# PCB-SLIDER60_v11-16.net
KiCad netlist of a schematic drawn in EAGLE
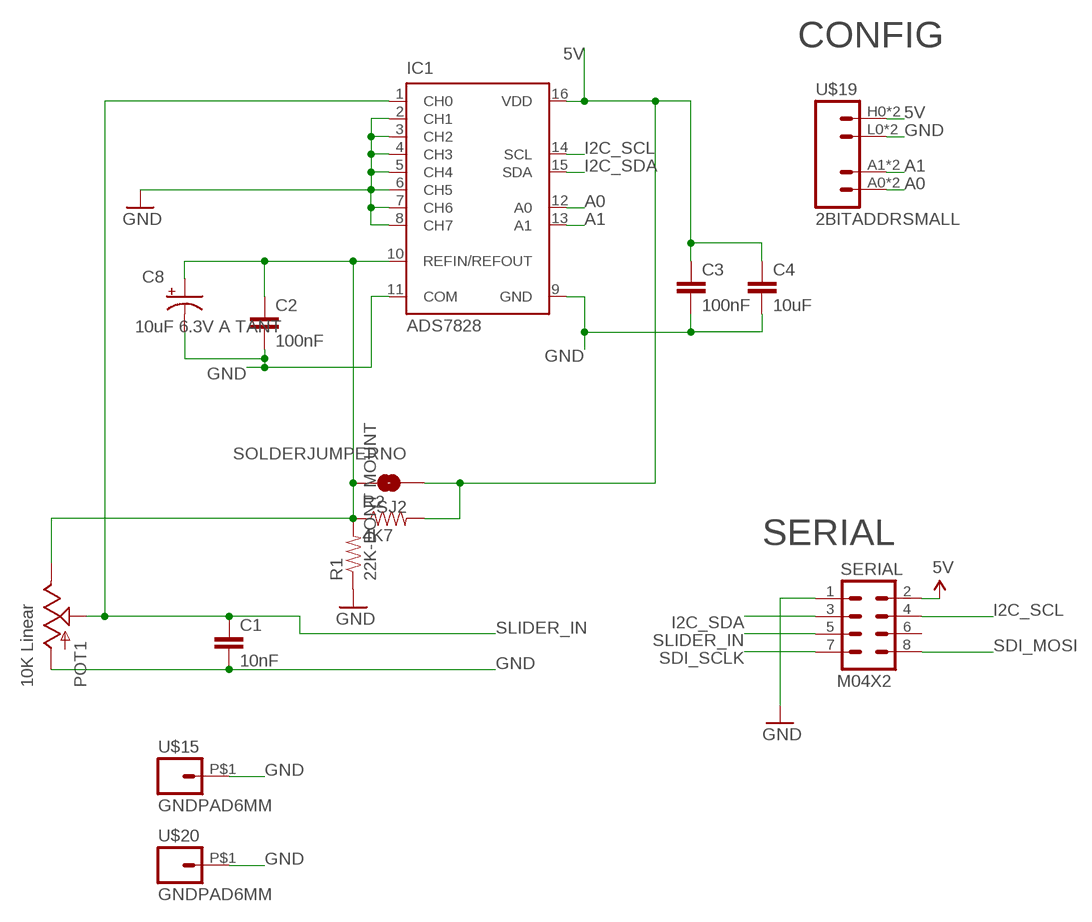
[diagram p0: schematic, sheet 1]

(export (version "E")
  (design (tool "Eeschema 10.0.6"))
  (components
    (comp (ref "C1")
      (value "10nF")
      (footprint "eagle-import:0603-CAP")
      (libsource (lib "eagle-import") (part "CAP0603-CAP"))
    )
    (comp (ref "C2")
      (value "100nF")
      (footprint "eagle-import:0603-CAP")
      (libsource (lib "eagle-import") (part "CAP0603-CAP"))
    )
    (comp (ref "C3")
      (value "100nF")
      (footprint "eagle-import:0603-CAP")
      (libsource (lib "eagle-import") (part "CAP0603-CAP"))
    )
    (comp (ref "C4")
      (value "10uF")
      (footprint "eagle-import:0805")
      (libsource (lib "eagle-import") (part "CAP0805"))
    )
    (comp (ref "C8")
      (value "10uF 6.3V A TANT")
      (footprint "eagle-import:EIA3216")
      (libsource (lib "eagle-import") (part "CAP_POL1206"))
    )
    (comp (ref "IC1")
      (value "ADS7828")
      (footprint "eagle-import:TSSOP16-PW")
      (fields (field (name "MF") "TEXAS INSTRUMENTS") (field (name "MPN") "ADS7828E/250"))
      (libsource (lib "eagle-import") (part "ADS7828"))
    )
    (comp (ref "POT1")
      (value "10K Linear")
      (footprint "eagle-import:SLIDER60")
      (libsource (lib "eagle-import") (part "SLIDER60"))
    )
    (comp (ref "R1")
      (value "22K-DONT MOUNT")
      (footprint "eagle-import:0603-RES")
      (libsource (lib "eagle-import") (part "RESISTOR0603-RES"))
    )
    (comp (ref "R2")
      (value "4K7")
      (footprint "eagle-import:0603-RES")
      (libsource (lib "eagle-import") (part "RESISTOR0603-RES"))
    )
    (comp (ref "SERIAL")
      (value "M04X2")
      (footprint "eagle-import:2X4")
      (libsource (lib "eagle-import") (part "M04X2"))
    )
    (comp (ref "SJ2")
      (value "SOLDERJUMPERNO")
      (footprint "eagle-import:SJ_2S-NO")
      (libsource (lib "eagle-import") (part "SOLDERJUMPERNO"))
    )
    (comp (ref "U$15")
      (value "GNDPAD6MM")
      (footprint "eagle-import:3.2MMPAD6MM")
      (libsource (lib "eagle-import") (part "GNDPAD6MM"))
    )
    (comp (ref "U$19")
      (value "2BITADDRSMALL")
      (footprint "eagle-import:2BITADDR_SMALL")
      (libsource (lib "eagle-import") (part "2BITADDRSMALL"))
    )
    (comp (ref "U$20")
      (value "GNDPAD6MM")
      (footprint "eagle-import:3.2MMPAD6MM")
      (libsource (lib "eagle-import") (part "GNDPAD6MM"))
    )
  )
  (nets
    (net (code "1") (name "/A0") (class "Default")
      (node (ref "IC1") (pin "12") (pinfunction "A0_12") (pintype "input"))
      (node (ref "U$19") (pin "A0") (pinfunction "A1_A0") (pintype "passive"))
      (node (ref "U$19") (pin "AS0") (pinfunction "A1_AS0") (pintype "passive"))
    )
    (net (code "2") (name "/A1") (class "Default")
      (node (ref "IC1") (pin "13") (pinfunction "A1_13") (pintype "input"))
      (node (ref "U$19") (pin "A1") (pinfunction "A2_A1") (pintype "passive"))
      (node (ref "U$19") (pin "AS1") (pinfunction "A2_AS1") (pintype "passive"))
    )
    (net (code "3") (name "/I2C_SCL") (class "Default")
      (node (ref "IC1") (pin "14") (pinfunction "SCL_14") (pintype "input"))
      (node (ref "SERIAL") (pin "4") (pinfunction "4_4") (pintype "passive"))
    )
    (net (code "4") (name "/I2C_SDA") (class "Default")
      (node (ref "IC1") (pin "15") (pinfunction "SDA_15") (pintype "bidirectional"))
      (node (ref "SERIAL") (pin "3") (pinfunction "3_3") (pintype "passive"))
    )
    (net (code "5") (name "/SDI_MOSI") (class "Default")
      (node (ref "SERIAL") (pin "8") (pinfunction "8_8") (pintype "passive"))
    )
    (net (code "6") (name "/SDI_SCLK") (class "Default")
      (node (ref "SERIAL") (pin "7") (pinfunction "7_7") (pintype "passive"))
    )
    (net (code "7") (name "/SLIDER_IN") (class "Default")
      (node (ref "C1") (pin "1") (pinfunction "1_1") (pintype "passive"))
      (node (ref "IC1") (pin "1") (pinfunction "CH0_1") (pintype "input"))
      (node (ref "POT1") (pin "2A") (pinfunction "S_2A") (pintype "passive"))
      (node (ref "SERIAL") (pin "5") (pinfunction "5_5") (pintype "passive"))
    )
    (net (code "8") (name "5V") (class "Default")
      (node (ref "C3") (pin "1") (pinfunction "1_1") (pintype "passive"))
      (node (ref "C4") (pin "1") (pinfunction "1_1") (pintype "passive"))
      (node (ref "IC1") (pin "16") (pinfunction "VDD_16") (pintype "power_in"))
      (node (ref "R2") (pin "2") (pinfunction "2_2") (pintype "passive"))
      (node (ref "SERIAL") (pin "2") (pinfunction "2_2") (pintype "passive"))
      (node (ref "SJ2") (pin "1") (pinfunction "1_1") (pintype "passive"))
      (node (ref "U$19") (pin "H0") (pinfunction "VCC_H0") (pintype "passive"))
      (node (ref "U$19") (pin "H1") (pinfunction "VCC_H1") (pintype "passive"))
    )
    (net (code "9") (name "GND") (class "Default")
      (node (ref "C1") (pin "2") (pinfunction "2_2") (pintype "passive"))
      (node (ref "C2") (pin "2") (pinfunction "2_2") (pintype "passive"))
      (node (ref "C3") (pin "2") (pinfunction "2_2") (pintype "passive"))
      (node (ref "C4") (pin "2") (pinfunction "2_2") (pintype "passive"))
      (node (ref "C8") (pin "C") (pinfunction "-_C") (pintype "passive"))
      (node (ref "IC1") (pin "11") (pinfunction "COM_11") (pintype "input"))
      (node (ref "IC1") (pin "2") (pinfunction "CH1_2") (pintype "input"))
      (node (ref "IC1") (pin "3") (pinfunction "CH2_3") (pintype "input"))
      (node (ref "IC1") (pin "4") (pinfunction "CH3_4") (pintype "input"))
      (node (ref "IC1") (pin "5") (pinfunction "CH4_5") (pintype "input"))
      (node (ref "IC1") (pin "6") (pinfunction "CH5_6") (pintype "input"))
      (node (ref "IC1") (pin "7") (pinfunction "CH6_7") (pintype "input"))
      (node (ref "IC1") (pin "8") (pinfunction "CH7_8") (pintype "input"))
      (node (ref "IC1") (pin "9") (pinfunction "GND_9") (pintype "power_in"))
      (node (ref "POT1") (pin "3") (pinfunction "A_3") (pintype "passive"))
      (node (ref "R1") (pin "1") (pinfunction "1_1") (pintype "passive"))
      (node (ref "SERIAL") (pin "1") (pinfunction "1_1") (pintype "passive"))
      (node (ref "U$15") (pin "P$1") (pinfunction "1_P$1") (pintype "passive"))
      (node (ref "U$19") (pin "L0") (pinfunction "GND_L0") (pintype "passive"))
      (node (ref "U$19") (pin "L1") (pinfunction "GND_L1") (pintype "passive"))
      (node (ref "U$20") (pin "P$1") (pinfunction "1_P$1") (pintype "passive"))
    )
    (net (code "10") (name "Net-(C8-+)") (class "Default")
      (node (ref "C2") (pin "1") (pinfunction "1_1") (pintype "passive"))
      (node (ref "C8") (pin "A") (pinfunction "+_A") (pintype "passive"))
      (node (ref "IC1") (pin "10") (pinfunction "REFIN/REFOUT_10") (pintype "passive"))
      (node (ref "POT1") (pin "1") (pinfunction "E_1") (pintype "passive"))
      (node (ref "R1") (pin "2") (pinfunction "2_2") (pintype "passive"))
      (node (ref "R2") (pin "1") (pinfunction "1_1") (pintype "passive"))
      (node (ref "SJ2") (pin "2") (pinfunction "2_2") (pintype "passive"))
    )
    (net (code "11") (name "unconnected-(SERIAL-Pad6)") (class "Default")
      (node (ref "SERIAL") (pin "6") (pinfunction "6_6") (pintype "passive"))
    )
  )
)
